# 04_EEPROM_FLASH.net
KiCad netlist of a schematic drawn in Altium Designer
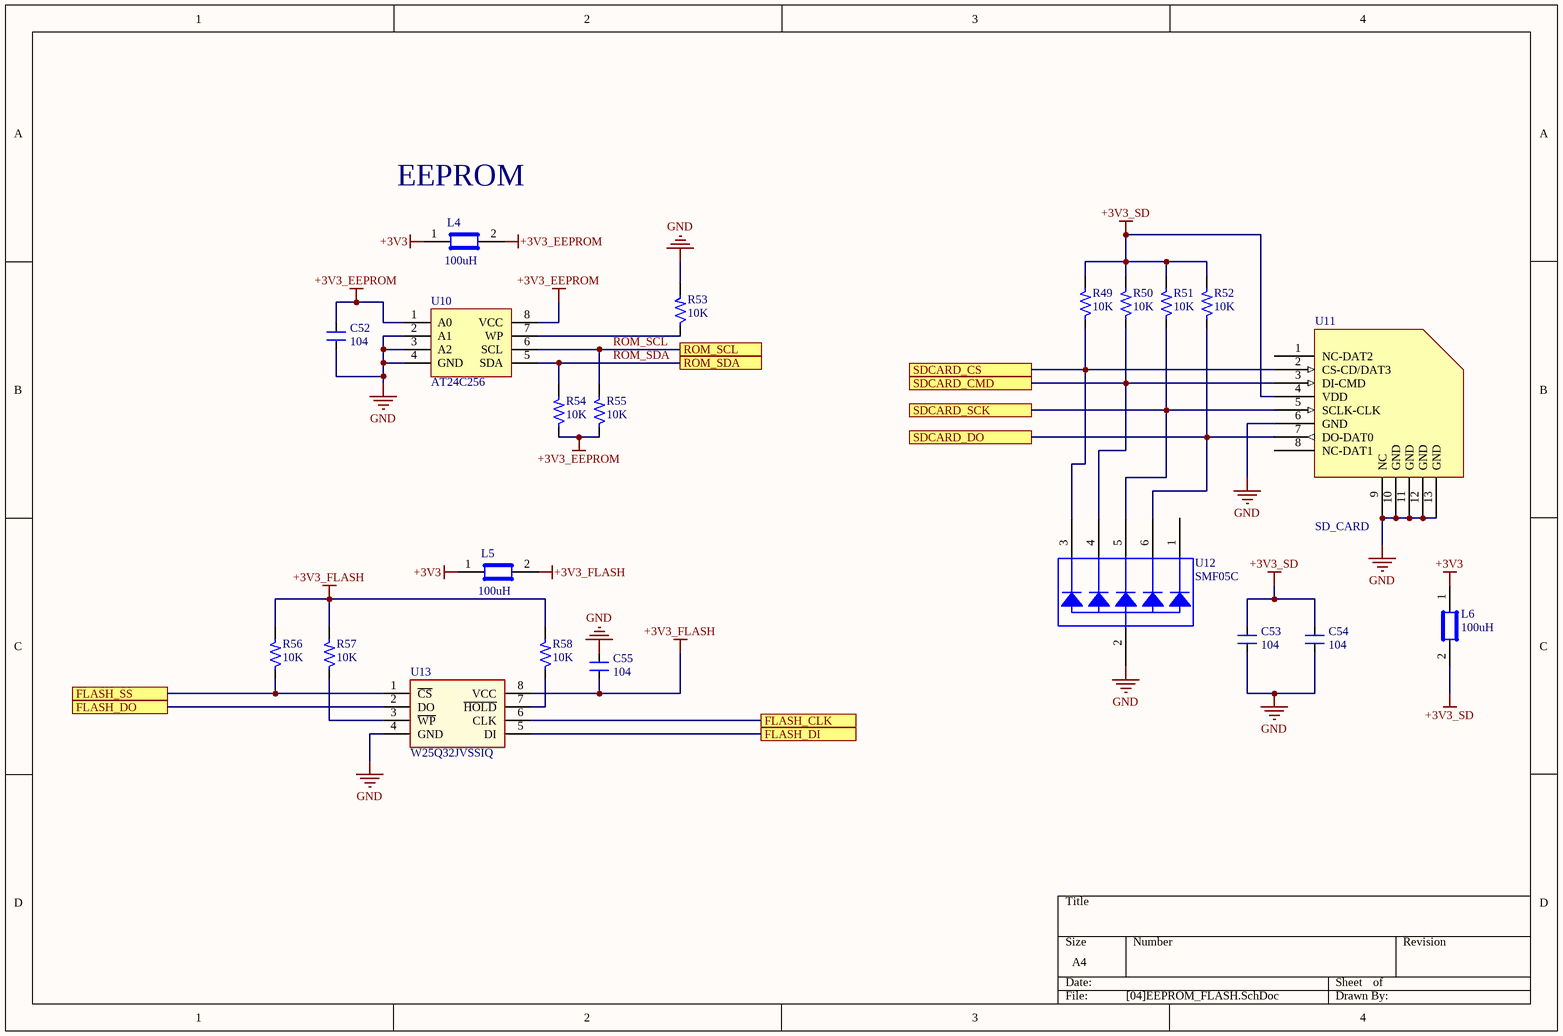
[diagram p0: [04]EEPROM_FLASH.SchDoc]

(export (version "E")
  (design (tool "Eeschema 10.0.6"))
  (components
    (comp (ref "C52")
      (value "104")
      (footprint "C0603 SMT")
      (description "Cap SMD")
      (libsource (lib "GPS_Traking_V1_1") (part "CM"))
    )
    (comp (ref "C53")
      (value "104")
      (footprint "C0603 SMT")
      (description "Cap SMD")
      (libsource (lib "GPS_Traking_V1_1") (part "CM"))
    )
    (comp (ref "C54")
      (value "104")
      (footprint "C0603 SMT")
      (description "Cap SMD")
      (libsource (lib "GPS_Traking_V1_1") (part "CM"))
    )
    (comp (ref "C55")
      (value "104")
      (footprint "C0603 SMT")
      (description "Cap SMD")
      (libsource (lib "GPS_Traking_V1_1") (part "CM"))
    )
    (comp (ref "L4")
      (value "100uH")
      (footprint "R0805")
      (description "100uH 0805")
      (libsource (lib "GPS_Traking_V1_1") (part "Ferrite Bead"))
    )
    (comp (ref "L5")
      (value "100uH")
      (footprint "R0805")
      (description "100uH 0805")
      (libsource (lib "GPS_Traking_V1_1") (part "Ferrite Bead"))
    )
    (comp (ref "L6")
      (value "100uH")
      (footprint "R0805")
      (description "100uH 0805")
      (libsource (lib "GPS_Traking_V1_1") (part "Ferrite Bead"))
    )
    (comp (ref "R49")
      (value "10K")
      (footprint "R0603 -SMT")
      (description "Resistor SMD")
      (libsource (lib "GPS_Traking_V1_1") (part "RM"))
    )
    (comp (ref "R50")
      (value "10K")
      (footprint "R0603 -SMT")
      (description "Resistor SMD")
      (libsource (lib "GPS_Traking_V1_1") (part "RM"))
    )
    (comp (ref "R51")
      (value "10K")
      (footprint "R0603 -SMT")
      (description "Resistor SMD")
      (libsource (lib "GPS_Traking_V1_1") (part "RM"))
    )
    (comp (ref "R52")
      (value "10K")
      (footprint "R0603 -SMT")
      (description "Resistor SMD")
      (libsource (lib "GPS_Traking_V1_1") (part "RM"))
    )
    (comp (ref "R53")
      (value "10K")
      (footprint "R0603 -SMT")
      (description "Resistor SMD")
      (libsource (lib "GPS_Traking_V1_1") (part "RM"))
    )
    (comp (ref "R54")
      (value "10K")
      (footprint "R0603 -SMT")
      (description "Resistor SMD")
      (libsource (lib "GPS_Traking_V1_1") (part "RM"))
    )
    (comp (ref "R55")
      (value "10K")
      (footprint "R0603 -SMT")
      (description "Resistor SMD")
      (libsource (lib "GPS_Traking_V1_1") (part "RM"))
    )
    (comp (ref "R56")
      (value "10K")
      (footprint "R0603 -SMT")
      (description "Resistor SMD")
      (libsource (lib "GPS_Traking_V1_1") (part "RM"))
    )
    (comp (ref "R57")
      (value "10K")
      (footprint "R0603 -SMT")
      (description "Resistor SMD")
      (libsource (lib "GPS_Traking_V1_1") (part "RM"))
    )
    (comp (ref "R58")
      (value "10K")
      (footprint "R0603 -SMT")
      (description "Resistor SMD")
      (libsource (lib "GPS_Traking_V1_1") (part "RM"))
    )
    (comp (ref "U10")
      (value "AT24C256")
      (footprint "SO-8")
      (libsource (lib "GPS_Traking_V1_1") (part "AT24Cxx"))
    )
    (comp (ref "U11")
      (value "SD_CARD")
      (footprint "MICROSD2")
      (description "SD/MMC holder")
      (libsource (lib "My Library") (part "MicroSD"))
    )
    (comp (ref "U12")
      (value "SMF05C")
      (footprint "SOT_363_6")
      (description "ESD Protection")
      (libsource (lib "GPS_Traking_V1_1") (part "SMF05C"))
    )
    (comp (ref "U13")
      (value "W25Q32JVSSIQ")
      (footprint "SO-8 208")
      (description "FLASH 32MBIT 133MHZ 8SOP")
      (libsource (lib "GPS_Traking_V1_1") (part "W25Q32JV"))
    )
  )
  (nets
    (net (code "1") (name "+3V3") (class "Default")
      (node (ref "L4") (pin "1") (pinfunction "1_1") (pintype "passive"))
      (node (ref "L5") (pin "1") (pinfunction "1_1") (pintype "passive"))
      (node (ref "L6") (pin "1") (pinfunction "1_1") (pintype "passive"))
    )
    (net (code "2") (name "+3V3_EEPROM") (class "Default")
      (node (ref "C52") (pin "2") (pinfunction "2_2") (pintype "passive"))
      (node (ref "L4") (pin "2") (pinfunction "2_2") (pintype "passive"))
      (node (ref "R54") (pin "1") (pinfunction "1_1") (pintype "passive"))
      (node (ref "R55") (pin "1") (pinfunction "1_1") (pintype "passive"))
      (node (ref "U10") (pin "1") (pinfunction "A0_1") (pintype "passive"))
      (node (ref "U10") (pin "8") (pinfunction "VCC_8") (pintype "passive"))
    )
    (net (code "3") (name "+3V3_FLASH") (class "Default")
      (node (ref "C55") (pin "1") (pinfunction "1_1") (pintype "passive"))
      (node (ref "L5") (pin "2") (pinfunction "2_2") (pintype "passive"))
      (node (ref "R56") (pin "2") (pinfunction "2_2") (pintype "passive"))
      (node (ref "R57") (pin "2") (pinfunction "2_2") (pintype "passive"))
      (node (ref "R58") (pin "2") (pinfunction "2_2") (pintype "passive"))
      (node (ref "U13") (pin "8") (pinfunction "VCC_8") (pintype "passive"))
    )
    (net (code "4") (name "+3V3_SD") (class "Default")
      (node (ref "C53") (pin "2") (pinfunction "2_2") (pintype "passive"))
      (node (ref "C54") (pin "2") (pinfunction "2_2") (pintype "passive"))
      (node (ref "L6") (pin "2") (pinfunction "2_2") (pintype "passive"))
      (node (ref "R49") (pin "2") (pinfunction "2_2") (pintype "passive"))
      (node (ref "R50") (pin "2") (pinfunction "2_2") (pintype "passive"))
      (node (ref "R51") (pin "2") (pinfunction "2_2") (pintype "passive"))
      (node (ref "R52") (pin "2") (pinfunction "2_2") (pintype "passive"))
      (node (ref "U11") (pin "4") (pinfunction "VDD_4") (pintype "passive"))
    )
    (net (code "5") (name "/FLASH_CLK") (class "Default")
      (node (ref "U13") (pin "6") (pinfunction "CLK_6") (pintype "passive"))
    )
    (net (code "6") (name "/FLASH_DI") (class "Default")
      (node (ref "U13") (pin "5") (pinfunction "DI_5") (pintype "passive"))
    )
    (net (code "7") (name "/FLASH_DO") (class "Default")
      (node (ref "U13") (pin "2") (pinfunction "DO_2") (pintype "passive"))
    )
    (net (code "8") (name "/FLASH_SS") (class "Default")
      (node (ref "R56") (pin "1") (pinfunction "1_1") (pintype "passive"))
      (node (ref "U13") (pin "1") (pinfunction "~{CS}_1") (pintype "passive"))
    )
    (net (code "9") (name "/ROM_SCL") (class "Default")
      (node (ref "R55") (pin "2") (pinfunction "2_2") (pintype "passive"))
      (node (ref "U10") (pin "6") (pinfunction "SCL_6") (pintype "passive"))
    )
    (net (code "10") (name "/ROM_SDA") (class "Default")
      (node (ref "R54") (pin "2") (pinfunction "2_2") (pintype "passive"))
      (node (ref "U10") (pin "5") (pinfunction "SDA_5") (pintype "passive"))
    )
    (net (code "11") (name "/SDCARD_CMD") (class "Default")
      (node (ref "R50") (pin "1") (pinfunction "1_1") (pintype "passive"))
      (node (ref "U11") (pin "3") (pinfunction "DI-CMD_3") (pintype "input"))
      (node (ref "U12") (pin "4") (pinfunction "K3_4") (pintype "passive"))
    )
    (net (code "12") (name "/SDCARD_CS") (class "Default")
      (node (ref "R49") (pin "1") (pinfunction "1_1") (pintype "passive"))
      (node (ref "U11") (pin "2") (pinfunction "CS-CD/DAT3_2") (pintype "input"))
      (node (ref "U12") (pin "3") (pinfunction "K2_3") (pintype "passive"))
    )
    (net (code "13") (name "/SDCARD_DO") (class "Default")
      (node (ref "R52") (pin "1") (pinfunction "1_1") (pintype "passive"))
      (node (ref "U11") (pin "7") (pinfunction "DO-DAT0_7") (pintype "output"))
      (node (ref "U12") (pin "6") (pinfunction "K5_6") (pintype "passive"))
    )
    (net (code "14") (name "/SDCARD_SCK") (class "Default")
      (node (ref "R51") (pin "1") (pinfunction "1_1") (pintype "passive"))
      (node (ref "U11") (pin "5") (pinfunction "SCLK-CLK_5") (pintype "input"))
      (node (ref "U12") (pin "5") (pinfunction "K4_5") (pintype "power_in"))
    )
    (net (code "15") (name "GND") (class "Default")
      (node (ref "C52") (pin "1") (pinfunction "1_1") (pintype "passive"))
      (node (ref "C53") (pin "1") (pinfunction "1_1") (pintype "passive"))
      (node (ref "C54") (pin "1") (pinfunction "1_1") (pintype "passive"))
      (node (ref "C55") (pin "2") (pinfunction "2_2") (pintype "passive"))
      (node (ref "R53") (pin "2") (pinfunction "2_2") (pintype "passive"))
      (node (ref "U10") (pin "2") (pinfunction "A1_2") (pintype "passive"))
      (node (ref "U10") (pin "3") (pinfunction "A2_3") (pintype "passive"))
      (node (ref "U10") (pin "4") (pinfunction "GND_4") (pintype "passive"))
      (node (ref "U11") (pin "10") (pinfunction "GND_10") (pintype "passive"))
      (node (ref "U11") (pin "11") (pinfunction "GND_11") (pintype "passive"))
      (node (ref "U11") (pin "12") (pinfunction "GND_12") (pintype "passive"))
      (node (ref "U11") (pin "13") (pinfunction "GND_13") (pintype "passive"))
      (node (ref "U11") (pin "6") (pinfunction "GND_6") (pintype "passive"))
      (node (ref "U11") (pin "9") (pinfunction "NC_9") (pintype "passive"))
      (node (ref "U12") (pin "2") (pinfunction "A_2") (pintype "power_in"))
      (node (ref "U13") (pin "4") (pinfunction "GND_4") (pintype "passive"))
    )
    (net (code "16") (name "Net-(U10-WP)") (class "Default")
      (node (ref "R53") (pin "1") (pinfunction "1_1") (pintype "passive"))
      (node (ref "U10") (pin "7") (pinfunction "WP_7") (pintype "passive"))
    )
    (net (code "17") (name "Net-(U13-~{HOLD})") (class "Default")
      (node (ref "R58") (pin "1") (pinfunction "1_1") (pintype "passive"))
      (node (ref "U13") (pin "7") (pinfunction "~{HOLD}_7") (pintype "passive"))
    )
    (net (code "18") (name "Net-(U13-~{WP})") (class "Default")
      (node (ref "R57") (pin "1") (pinfunction "1_1") (pintype "passive"))
      (node (ref "U13") (pin "3") (pinfunction "~{WP}_3") (pintype "passive"))
    )
    (net (code "19") (name "unconnected-(U11-NC-DAT1-Pad8)") (class "Default")
      (node (ref "U11") (pin "8") (pinfunction "NC-DAT1_8") (pintype "passive"))
    )
    (net (code "20") (name "unconnected-(U11-NC-DAT2-Pad1)") (class "Default")
      (node (ref "U11") (pin "1") (pinfunction "NC-DAT2_1") (pintype "passive"))
    )
    (net (code "21") (name "unconnected-(U12-K1-Pad1)") (class "Default")
      (node (ref "U12") (pin "1") (pinfunction "K1_1") (pintype "passive"))
    )
  )
)
